# PressureSensor.net
KiCad netlist of a schematic drawn in Altium Designer
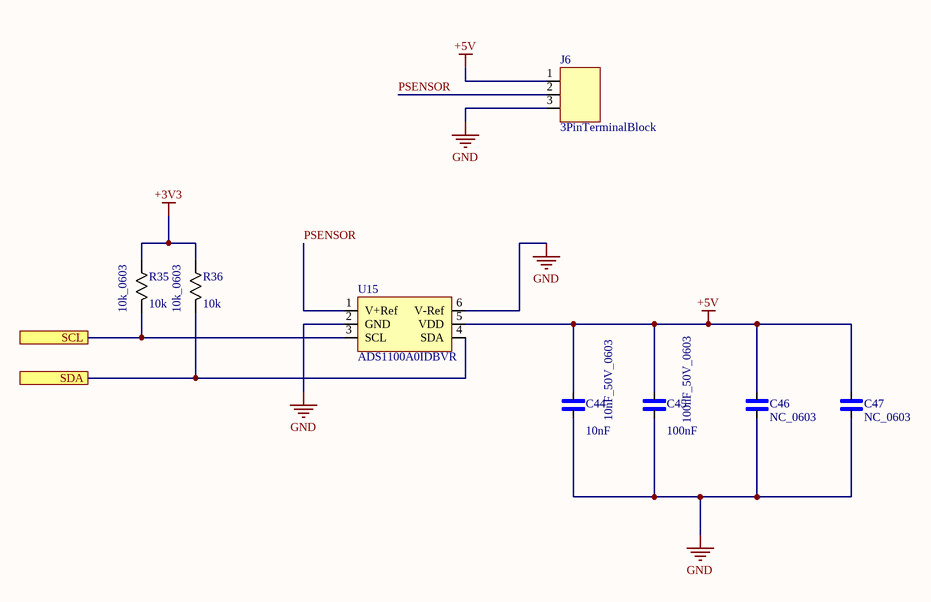
[diagram p0: PressureSensor.SchDoc]

(export (version "E")
  (design (tool "Eeschema 10.0.6"))
  (components
    (comp (ref "C44")
      (value "10nF_50V_0603")
      (footprint "0603")
      (fields
        (field (name "MANUFACTURER") "Murata")
        (field (name "MANUFACTURER PART NUMBER") "GRM188R71H103KA01D")
        (field (name "TOLERANCE") "10%")
        (field (name "CAPACITANCE") "10nF")
      )
      (libsource (lib "Capacitors") (part "10nF_50V_0603"))
    )
    (comp (ref "C45")
      (value "100nF_50V_0603")
      (footprint "0603")
      (fields
        (field (name "MANUFACTURER") "Murata")
        (field (name "MANUFACTURER PART NUMBER") "GRM188R71H104KA93D")
        (field (name "TOLERANCE") "10%")
        (field (name "CAPACITANCE") "100nF")
      )
      (libsource (lib "Capacitors") (part "100nF_50V_0603"))
    )
    (comp (ref "C46") (value "NC_0603") (footprint "0603") (libsource (lib "Capacitors") (part "NC_0603")))
    (comp (ref "C47") (value "NC_0603") (footprint "0603") (libsource (lib "Capacitors") (part "NC_0603")))
    (comp (ref "J6")
      (value "3PinTerminalBlock")
      (footprint "3 POS 5mm Pitch")
      (description "3 Position terminal block")
      (libsource (lib "Connectors") (part "3PinTerminalBlock"))
    )
    (comp (ref "R35")
      (value "10k_0603")
      (footprint "0603")
      (fields
        (field (name "MANUFACTURER") "Panasonic")
        (field (name "MANUFACTURER PART NUMBER") "ERJ-3EKF1002V")
        (field (name "TOLERANCE") "1%")
        (field (name "RESISTANCE") "10k")
      )
      (libsource (lib "Resistors") (part "10k_0603"))
    )
    (comp (ref "R36")
      (value "10k_0603")
      (footprint "0603")
      (fields
        (field (name "MANUFACTURER") "Panasonic")
        (field (name "MANUFACTURER PART NUMBER") "ERJ-3EKF1002V")
        (field (name "TOLERANCE") "1%")
        (field (name "RESISTANCE") "10k")
      )
      (libsource (lib "Resistors") (part "10k_0603"))
    )
    (comp (ref "U15")
      (value "ADS1100A0IDBVR")
      (footprint "ADS1100A0IDBVR")
      (description "Self-Calibrating, 16-Bit Analog-to-Digital Converter 6-SOT-23 -40 to 85")
      (libsource (lib "MiscComponents") (part "ADS1100A0IDBVR"))
    )
  )
  (nets
    (net (code "1") (name "+3V3") (class "Default")
      (node (ref "R35") (pin "2") (pinfunction "2_2") (pintype "passive"))
      (node (ref "R36") (pin "2") (pinfunction "2_2") (pintype "passive"))
    )
    (net (code "2") (name "+5V") (class "Default")
      (node (ref "C44") (pin "2") (pinfunction "2_2") (pintype "passive"))
      (node (ref "C45") (pin "2") (pinfunction "2_2") (pintype "passive"))
      (node (ref "C46") (pin "2") (pinfunction "2_2") (pintype "passive"))
      (node (ref "C47") (pin "2") (pinfunction "2_2") (pintype "passive"))
      (node (ref "J6") (pin "1") (pintype "passive"))
      (node (ref "U15") (pin "5") (pinfunction "VDD_5") (pintype "passive"))
    )
    (net (code "3") (name "/PSENSOR") (class "Default")
      (node (ref "J6") (pin "2") (pintype "passive"))
      (node (ref "U15") (pin "1") (pinfunction "V+Ref_1") (pintype "passive"))
    )
    (net (code "4") (name "/SCL") (class "Default")
      (node (ref "R35") (pin "1") (pinfunction "1_1") (pintype "passive"))
      (node (ref "U15") (pin "3") (pinfunction "SCL_3") (pintype "passive"))
    )
    (net (code "5") (name "/SDA") (class "Default")
      (node (ref "R36") (pin "1") (pinfunction "1_1") (pintype "passive"))
      (node (ref "U15") (pin "4") (pinfunction "SDA_4") (pintype "passive"))
    )
    (net (code "6") (name "GND") (class "Default")
      (node (ref "C44") (pin "1") (pinfunction "1_1") (pintype "passive"))
      (node (ref "C45") (pin "1") (pinfunction "1_1") (pintype "passive"))
      (node (ref "C46") (pin "1") (pinfunction "1_1") (pintype "passive"))
      (node (ref "C47") (pin "1") (pinfunction "1_1") (pintype "passive"))
      (node (ref "J6") (pin "3") (pintype "passive"))
      (node (ref "U15") (pin "2") (pinfunction "GND_2") (pintype "passive"))
      (node (ref "U15") (pin "6") (pinfunction "V-Ref_6") (pintype "passive"))
    )
  )
)
